# vca.net
KiCad netlist of a schematic drawn in EAGLE
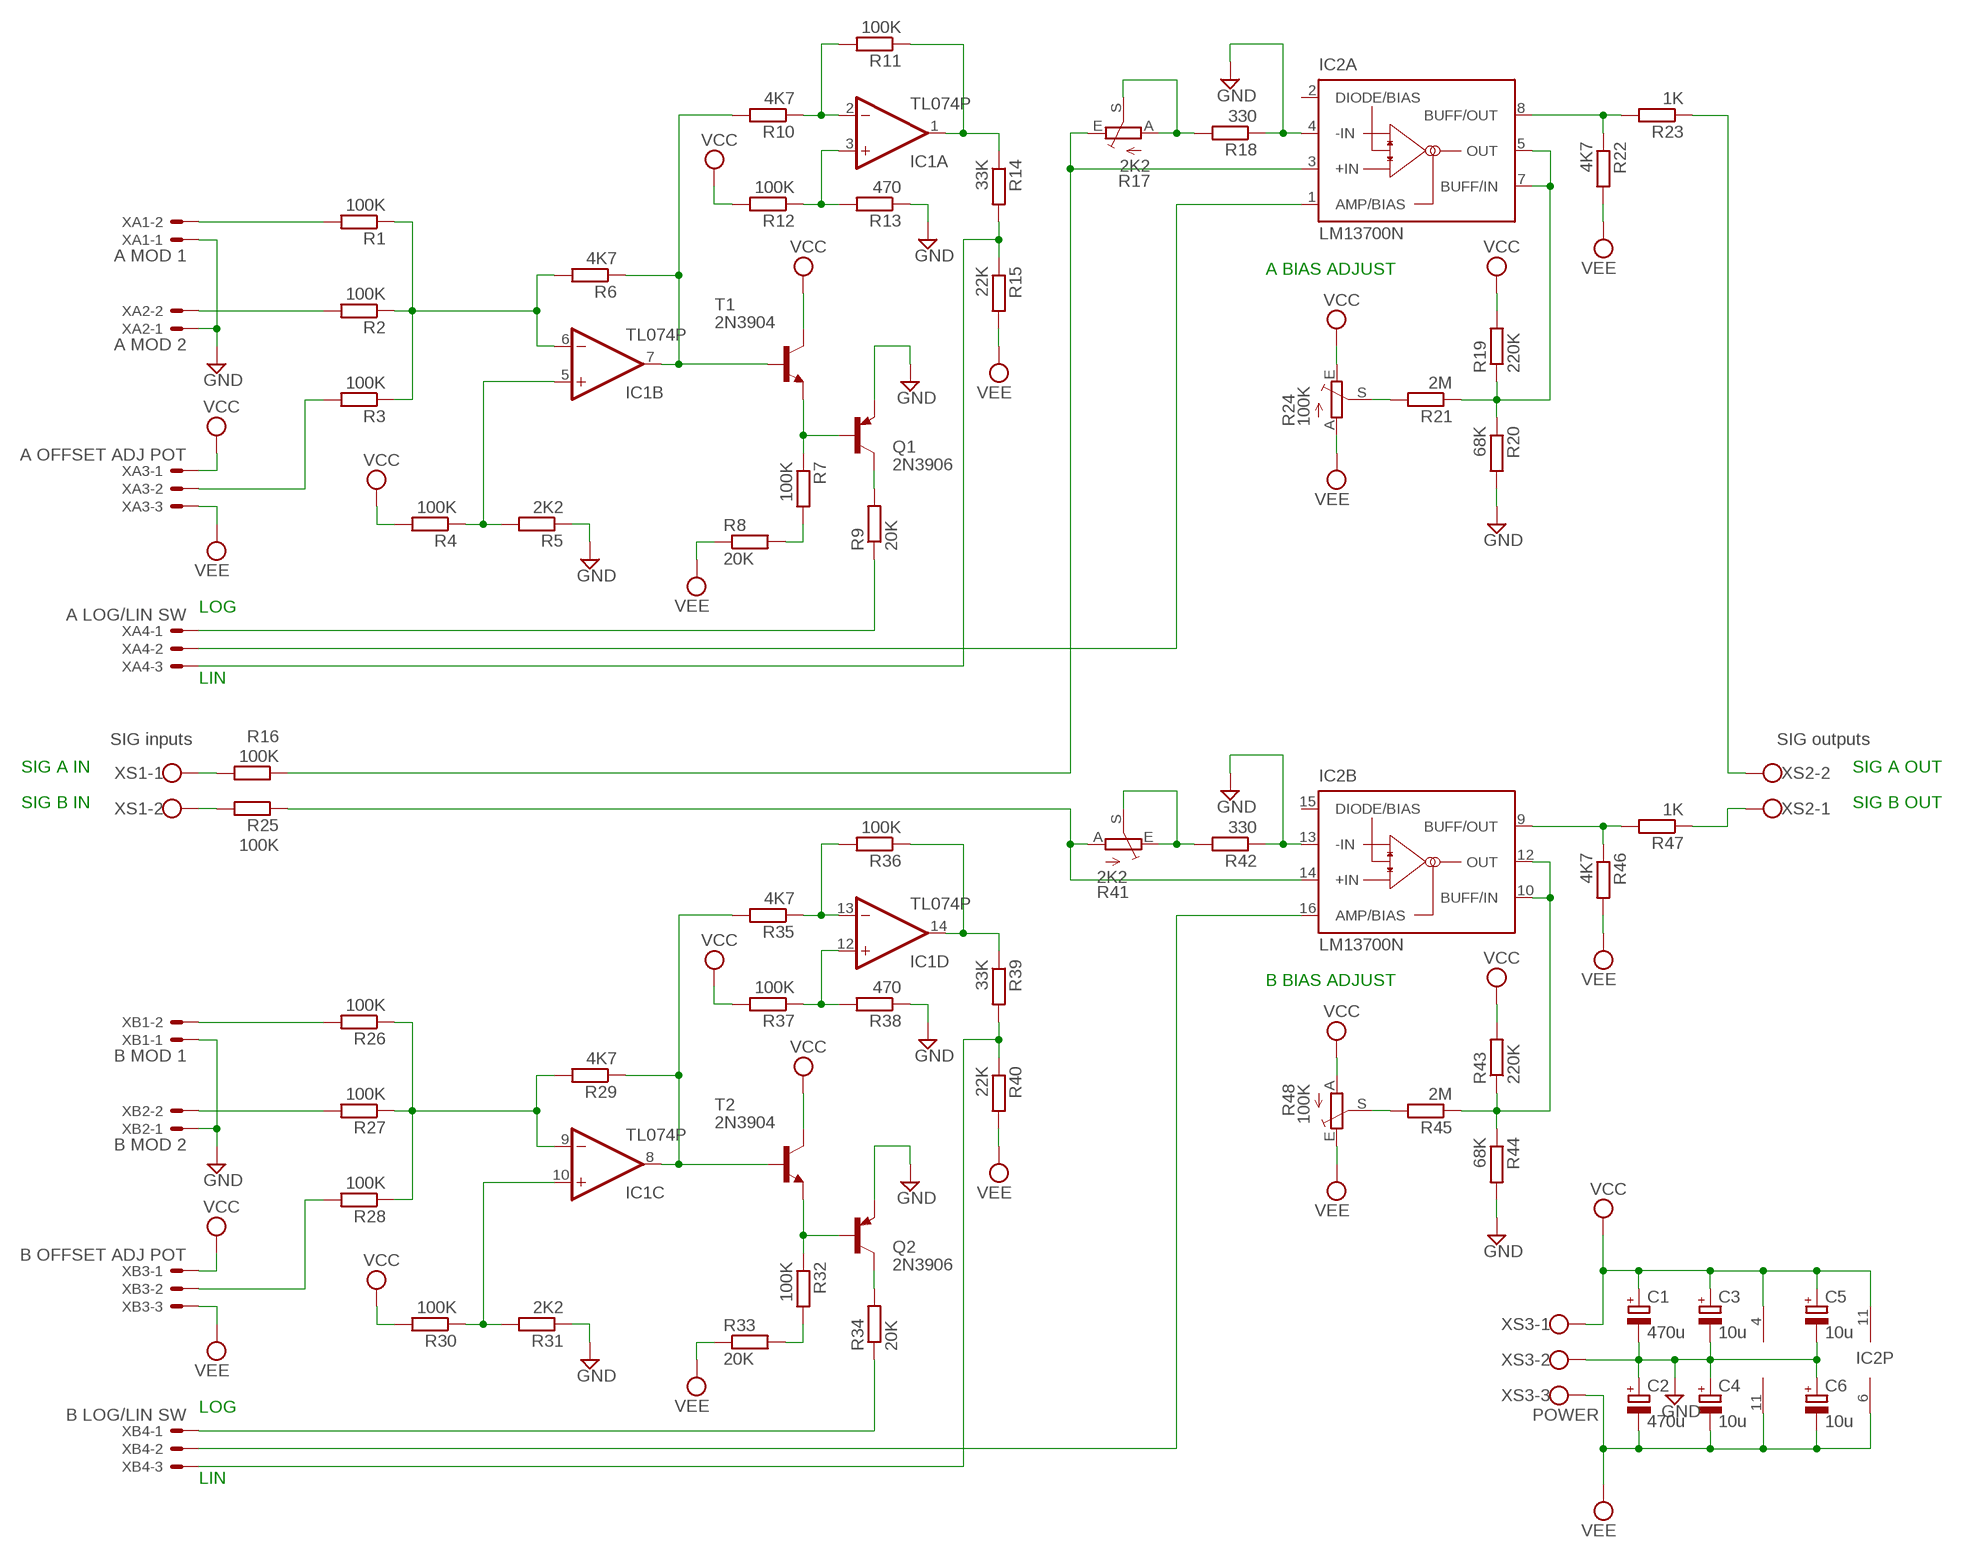
[diagram p0: schematic, sheet 1]

(export (version "E")
  (design (tool "Eeschema 10.0.6"))
  (components
    (comp (ref "C1")
      (value "470u")
      (footprint "eagle-import:E2,5-6")
      (libsource (lib "eagle-import") (part "CPOL-EUE2.5-6"))
    )
    (comp (ref "C2")
      (value "470u")
      (footprint "eagle-import:E2,5-6")
      (libsource (lib "eagle-import") (part "CPOL-EUE2.5-6"))
    )
    (comp (ref "C3")
      (value "10u")
      (footprint "eagle-import:E1,8-4")
      (libsource (lib "eagle-import") (part "CPOL-EUE1.8-4"))
    )
    (comp (ref "C4")
      (value "10u")
      (footprint "eagle-import:E1,8-4")
      (libsource (lib "eagle-import") (part "CPOL-EUE1.8-4"))
    )
    (comp (ref "C5")
      (value "10u")
      (footprint "eagle-import:E1,8-4")
      (libsource (lib "eagle-import") (part "CPOL-EUE1.8-4"))
    )
    (comp (ref "C6")
      (value "10u")
      (footprint "eagle-import:E1,8-4")
      (libsource (lib "eagle-import") (part "CPOL-EUE1.8-4"))
    )
    (comp (ref "IC1")
      (value "TL074P")
      (footprint "eagle-import:DIL14")
      (libsource (lib "eagle-import") (part "TL074P"))
    )
    (comp (ref "IC2")
      (value "LM13700N")
      (footprint "eagle-import:DIL16")
      (libsource (lib "eagle-import") (part "LM13600NA"))
    )
    (comp (ref "Q1")
      (value "2N3906")
      (footprint "eagle-import:TO92")
      (libsource (lib "eagle-import") (part "2N3906"))
    )
    (comp (ref "Q2")
      (value "2N3906")
      (footprint "eagle-import:TO92")
      (libsource (lib "eagle-import") (part "2N3906"))
    )
    (comp (ref "R1")
      (value "100K")
      (footprint "eagle-import:0204_7")
      (libsource (lib "eagle-import") (part "R-EU_0204/7"))
    )
    (comp (ref "R2")
      (value "100K")
      (footprint "eagle-import:0204_7")
      (libsource (lib "eagle-import") (part "R-EU_0204/7"))
    )
    (comp (ref "R3")
      (value "100K")
      (footprint "eagle-import:0204_7")
      (libsource (lib "eagle-import") (part "R-EU_0204/7"))
    )
    (comp (ref "R4")
      (value "100K")
      (footprint "eagle-import:0204_7")
      (libsource (lib "eagle-import") (part "R-EU_0204/7"))
    )
    (comp (ref "R5")
      (value "2K2")
      (footprint "eagle-import:0204_7")
      (libsource (lib "eagle-import") (part "R-EU_0204/7"))
    )
    (comp (ref "R6")
      (value "4K7")
      (footprint "eagle-import:0204_7")
      (libsource (lib "eagle-import") (part "R-EU_0204/7"))
    )
    (comp (ref "R7")
      (value "100K")
      (footprint "eagle-import:0204_7")
      (libsource (lib "eagle-import") (part "R-EU_0204/7"))
    )
    (comp (ref "R8")
      (value "20K")
      (footprint "eagle-import:0204_7")
      (libsource (lib "eagle-import") (part "R-EU_0204/7"))
    )
    (comp (ref "R9")
      (value "20K")
      (footprint "eagle-import:0204_7")
      (libsource (lib "eagle-import") (part "R-EU_0204/7"))
    )
    (comp (ref "R10")
      (value "4K7")
      (footprint "eagle-import:0204_7")
      (libsource (lib "eagle-import") (part "R-EU_0204/7"))
    )
    (comp (ref "R11")
      (value "100K")
      (footprint "eagle-import:0204_7")
      (libsource (lib "eagle-import") (part "R-EU_0204/7"))
    )
    (comp (ref "R12")
      (value "100K")
      (footprint "eagle-import:0204_7")
      (libsource (lib "eagle-import") (part "R-EU_0204/7"))
    )
    (comp (ref "R13")
      (value "470")
      (footprint "eagle-import:0204_7")
      (libsource (lib "eagle-import") (part "R-EU_0204/7"))
    )
    (comp (ref "R14")
      (value "33K")
      (footprint "eagle-import:0204_7")
      (libsource (lib "eagle-import") (part "R-EU_0204/7"))
    )
    (comp (ref "R15")
      (value "22K")
      (footprint "eagle-import:0204_7")
      (libsource (lib "eagle-import") (part "R-EU_0204/7"))
    )
    (comp (ref "R16")
      (value "100K")
      (footprint "eagle-import:0204_7")
      (libsource (lib "eagle-import") (part "R-EU_0204/7"))
    )
    (comp (ref "R17")
      (value "2K2")
      (footprint "eagle-import:CA6V")
      (libsource (lib "eagle-import") (part "TRIM_EU-CA6V"))
    )
    (comp (ref "R18")
      (value "330")
      (footprint "eagle-import:0204_7")
      (libsource (lib "eagle-import") (part "R-EU_0204/7"))
    )
    (comp (ref "R19")
      (value "220K")
      (footprint "eagle-import:0204_7")
      (libsource (lib "eagle-import") (part "R-EU_0204/7"))
    )
    (comp (ref "R20")
      (value "68K")
      (footprint "eagle-import:0204_7")
      (libsource (lib "eagle-import") (part "R-EU_0204/7"))
    )
    (comp (ref "R21")
      (value "2M")
      (footprint "eagle-import:0204_7")
      (libsource (lib "eagle-import") (part "R-EU_0204/7"))
    )
    (comp (ref "R22")
      (value "4K7")
      (footprint "eagle-import:0204_7")
      (libsource (lib "eagle-import") (part "R-EU_0204/7"))
    )
    (comp (ref "R23")
      (value "1K")
      (footprint "eagle-import:0204_7")
      (libsource (lib "eagle-import") (part "R-EU_0204/7"))
    )
    (comp (ref "R24")
      (value "100K")
      (footprint "eagle-import:CA6V")
      (libsource (lib "eagle-import") (part "TRIM_EU-CA6V"))
    )
    (comp (ref "R25")
      (value "100K")
      (footprint "eagle-import:0204_7")
      (libsource (lib "eagle-import") (part "R-EU_0204/7"))
    )
    (comp (ref "R26")
      (value "100K")
      (footprint "eagle-import:0204_7")
      (libsource (lib "eagle-import") (part "R-EU_0204/7"))
    )
    (comp (ref "R27")
      (value "100K")
      (footprint "eagle-import:0204_7")
      (libsource (lib "eagle-import") (part "R-EU_0204/7"))
    )
    (comp (ref "R28")
      (value "100K")
      (footprint "eagle-import:0204_7")
      (libsource (lib "eagle-import") (part "R-EU_0204/7"))
    )
    (comp (ref "R29")
      (value "4K7")
      (footprint "eagle-import:0204_7")
      (libsource (lib "eagle-import") (part "R-EU_0204/7"))
    )
    (comp (ref "R30")
      (value "100K")
      (footprint "eagle-import:0204_7")
      (libsource (lib "eagle-import") (part "R-EU_0204/7"))
    )
    (comp (ref "R31")
      (value "2K2")
      (footprint "eagle-import:0204_7")
      (libsource (lib "eagle-import") (part "R-EU_0204/7"))
    )
    (comp (ref "R32")
      (value "100K")
      (footprint "eagle-import:0204_7")
      (libsource (lib "eagle-import") (part "R-EU_0204/7"))
    )
    (comp (ref "R33")
      (value "20K")
      (footprint "eagle-import:0204_7")
      (libsource (lib "eagle-import") (part "R-EU_0204/7"))
    )
    (comp (ref "R34")
      (value "20K")
      (footprint "eagle-import:0204_7")
      (libsource (lib "eagle-import") (part "R-EU_0204/7"))
    )
    (comp (ref "R35")
      (value "4K7")
      (footprint "eagle-import:0204_7")
      (libsource (lib "eagle-import") (part "R-EU_0204/7"))
    )
    (comp (ref "R36")
      (value "100K")
      (footprint "eagle-import:0204_7")
      (libsource (lib "eagle-import") (part "R-EU_0204/7"))
    )
    (comp (ref "R37")
      (value "100K")
      (footprint "eagle-import:0204_7")
      (libsource (lib "eagle-import") (part "R-EU_0204/7"))
    )
    (comp (ref "R38")
      (value "470")
      (footprint "eagle-import:0204_7")
      (libsource (lib "eagle-import") (part "R-EU_0204/7"))
    )
    (comp (ref "R39")
      (value "33K")
      (footprint "eagle-import:0204_7")
      (libsource (lib "eagle-import") (part "R-EU_0204/7"))
    )
    (comp (ref "R40")
      (value "22K")
      (footprint "eagle-import:0204_7")
      (libsource (lib "eagle-import") (part "R-EU_0204/7"))
    )
    (comp (ref "R41")
      (value "2K2")
      (footprint "eagle-import:CA6V")
      (libsource (lib "eagle-import") (part "TRIM_EU-CA6V"))
    )
    (comp (ref "R42")
      (value "330")
      (footprint "eagle-import:0204_7")
      (libsource (lib "eagle-import") (part "R-EU_0204/7"))
    )
    (comp (ref "R43")
      (value "220K")
      (footprint "eagle-import:0204_7")
      (libsource (lib "eagle-import") (part "R-EU_0204/7"))
    )
    (comp (ref "R44")
      (value "68K")
      (footprint "eagle-import:0204_7")
      (libsource (lib "eagle-import") (part "R-EU_0204/7"))
    )
    (comp (ref "R45")
      (value "2M")
      (footprint "eagle-import:0204_7")
      (libsource (lib "eagle-import") (part "R-EU_0204/7"))
    )
    (comp (ref "R46")
      (value "4K7")
      (footprint "eagle-import:0204_7")
      (libsource (lib "eagle-import") (part "R-EU_0204/7"))
    )
    (comp (ref "R47")
      (value "1K")
      (footprint "eagle-import:0204_7")
      (libsource (lib "eagle-import") (part "R-EU_0204/7"))
    )
    (comp (ref "R48")
      (value "100K")
      (footprint "eagle-import:CA6V")
      (libsource (lib "eagle-import") (part "TRIM_EU-CA6V"))
    )
    (comp (ref "T1")
      (value "2N3904")
      (footprint "eagle-import:TO92")
      (libsource (lib "eagle-import") (part "2N3904"))
    )
    (comp (ref "T2")
      (value "2N3904")
      (footprint "eagle-import:TO92")
      (libsource (lib "eagle-import") (part "2N3904"))
    )
    (comp (ref "XA1")
      (value "A MOD 1")
      (footprint "eagle-import:22-23-2021")
      (fields (field (name "MF") "MOLEX") (field (name "MPN") "22-23-2021"))
      (libsource (lib "eagle-import") (part "22-23-2021"))
    )
    (comp (ref "XA2")
      (value "A MOD 2")
      (footprint "eagle-import:22-23-2021")
      (fields (field (name "MF") "MOLEX") (field (name "MPN") "22-23-2021"))
      (libsource (lib "eagle-import") (part "22-23-2021"))
    )
    (comp (ref "XA3")
      (value "A OFFSET ADJ POT")
      (footprint "eagle-import:22-23-2031")
      (fields (field (name "MF") "MOLEX") (field (name "MPN") "22-23-2031"))
      (libsource (lib "eagle-import") (part "22-23-2031"))
    )
    (comp (ref "XA4")
      (value "A LOG/LIN SW")
      (footprint "eagle-import:22-23-2031")
      (fields (field (name "MF") "MOLEX") (field (name "MPN") "22-23-2031"))
      (libsource (lib "eagle-import") (part "22-23-2031"))
    )
    (comp (ref "XB1")
      (value "B MOD 1")
      (footprint "eagle-import:22-23-2021")
      (fields (field (name "MF") "MOLEX") (field (name "MPN") "22-23-2021"))
      (libsource (lib "eagle-import") (part "22-23-2021"))
    )
    (comp (ref "XB2")
      (value "B MOD 2")
      (footprint "eagle-import:22-23-2021")
      (fields (field (name "MF") "MOLEX") (field (name "MPN") "22-23-2021"))
      (libsource (lib "eagle-import") (part "22-23-2021"))
    )
    (comp (ref "XB3")
      (value "B OFFSET ADJ POT")
      (footprint "eagle-import:22-23-2031")
      (fields (field (name "MF") "MOLEX") (field (name "MPN") "22-23-2031"))
      (libsource (lib "eagle-import") (part "22-23-2031"))
    )
    (comp (ref "XB4")
      (value "B LOG/LIN SW")
      (footprint "eagle-import:22-23-2031")
      (fields (field (name "MF") "MOLEX") (field (name "MPN") "22-23-2031"))
      (libsource (lib "eagle-import") (part "22-23-2031"))
    )
    (comp (ref "XS1")
      (value "SIG inputs")
      (footprint "eagle-import:W237-102")
      (fields (field (name "MPN") "237-102"))
      (libsource (lib "eagle-import") (part "W237-102"))
    )
    (comp (ref "XS2")
      (value "SIG outputs")
      (footprint "eagle-import:W237-102")
      (fields (field (name "MPN") "237-102"))
      (libsource (lib "eagle-import") (part "W237-102"))
    )
    (comp (ref "XS3")
      (value "POWER")
      (footprint "eagle-import:W237-103")
      (fields (field (name "MPN") "237-103"))
      (libsource (lib "eagle-import") (part "W237-103"))
    )
  )
  (nets
    (net (code "1") (name "GND") (class "Default")
      (node (ref "C1") (pin "-") (pinfunction "-_-") (pintype "passive"))
      (node (ref "C2") (pin "+") (pinfunction "+_+") (pintype "passive"))
      (node (ref "C3") (pin "-") (pinfunction "-_-") (pintype "passive"))
      (node (ref "C4") (pin "+") (pinfunction "+_+") (pintype "passive"))
      (node (ref "C5") (pin "-") (pinfunction "-_-") (pintype "passive"))
      (node (ref "C6") (pin "+") (pinfunction "+_+") (pintype "passive"))
      (node (ref "IC2") (pin "13") (pinfunction "-IN_13") (pintype "input"))
      (node (ref "IC2") (pin "4") (pinfunction "-IN_4") (pintype "input"))
      (node (ref "Q1") (pin "3") (pinfunction "E_3") (pintype "passive"))
      (node (ref "Q2") (pin "3") (pinfunction "E_3") (pintype "passive"))
      (node (ref "R13") (pin "1") (pinfunction "1_1") (pintype "passive"))
      (node (ref "R18") (pin "1") (pinfunction "1_1") (pintype "passive"))
      (node (ref "R20") (pin "2") (pinfunction "2_2") (pintype "passive"))
      (node (ref "R31") (pin "1") (pinfunction "1_1") (pintype "passive"))
      (node (ref "R38") (pin "1") (pinfunction "1_1") (pintype "passive"))
      (node (ref "R42") (pin "1") (pinfunction "1_1") (pintype "passive"))
      (node (ref "R44") (pin "2") (pinfunction "2_2") (pintype "passive"))
      (node (ref "R5") (pin "1") (pinfunction "1_1") (pintype "passive"))
      (node (ref "XA1") (pin "1") (pinfunction "S_1") (pintype "passive"))
      (node (ref "XA2") (pin "1") (pinfunction "S_1") (pintype "passive"))
      (node (ref "XB1") (pin "1") (pinfunction "S_1") (pintype "passive"))
      (node (ref "XB2") (pin "1") (pinfunction "S_1") (pintype "passive"))
      (node (ref "XS3") (pin "2") (pinfunction "KL_2") (pintype "passive"))
    )
    (net (code "2") (name "Net-(IC1A-+IN)") (class "Default")
      (node (ref "IC1") (pin "3") (pinfunction "+IN_3") (pintype "input"))
      (node (ref "R12") (pin "1") (pinfunction "1_1") (pintype "passive"))
      (node (ref "R13") (pin "2") (pinfunction "2_2") (pintype "passive"))
    )
    (net (code "3") (name "Net-(IC1A--IN)") (class "Default")
      (node (ref "IC1") (pin "2") (pinfunction "-IN_2") (pintype "input"))
      (node (ref "R10") (pin "1") (pinfunction "1_1") (pintype "passive"))
      (node (ref "R11") (pin "2") (pinfunction "2_2") (pintype "passive"))
    )
    (net (code "4") (name "Net-(IC1A-OUT)") (class "Default")
      (node (ref "IC1") (pin "1") (pinfunction "OUT_1") (pintype "output"))
      (node (ref "R11") (pin "1") (pinfunction "1_1") (pintype "passive"))
      (node (ref "R14") (pin "1") (pinfunction "1_1") (pintype "passive"))
    )
    (net (code "5") (name "Net-(IC1B-+IN)") (class "Default")
      (node (ref "IC1") (pin "5") (pinfunction "+IN_5") (pintype "input"))
      (node (ref "R4") (pin "1") (pinfunction "1_1") (pintype "passive"))
      (node (ref "R5") (pin "2") (pinfunction "2_2") (pintype "passive"))
    )
    (net (code "6") (name "Net-(IC1B--IN)") (class "Default")
      (node (ref "IC1") (pin "6") (pinfunction "-IN_6") (pintype "input"))
      (node (ref "R1") (pin "1") (pinfunction "1_1") (pintype "passive"))
      (node (ref "R2") (pin "1") (pinfunction "1_1") (pintype "passive"))
      (node (ref "R3") (pin "1") (pinfunction "1_1") (pintype "passive"))
      (node (ref "R6") (pin "2") (pinfunction "2_2") (pintype "passive"))
    )
    (net (code "7") (name "Net-(IC1B-OUT)") (class "Default")
      (node (ref "IC1") (pin "7") (pinfunction "OUT_7") (pintype "output"))
      (node (ref "R10") (pin "2") (pinfunction "2_2") (pintype "passive"))
      (node (ref "R6") (pin "1") (pinfunction "1_1") (pintype "passive"))
      (node (ref "T1") (pin "2") (pinfunction "B_2") (pintype "passive"))
    )
    (net (code "8") (name "Net-(IC1C-+IN)") (class "Default")
      (node (ref "IC1") (pin "10") (pinfunction "+IN_10") (pintype "input"))
      (node (ref "R30") (pin "1") (pinfunction "1_1") (pintype "passive"))
      (node (ref "R31") (pin "2") (pinfunction "2_2") (pintype "passive"))
    )
    (net (code "9") (name "Net-(IC1C--IN)") (class "Default")
      (node (ref "IC1") (pin "9") (pinfunction "-IN_9") (pintype "input"))
      (node (ref "R26") (pin "1") (pinfunction "1_1") (pintype "passive"))
      (node (ref "R27") (pin "1") (pinfunction "1_1") (pintype "passive"))
      (node (ref "R28") (pin "1") (pinfunction "1_1") (pintype "passive"))
      (node (ref "R29") (pin "2") (pinfunction "2_2") (pintype "passive"))
    )
    (net (code "10") (name "Net-(IC1C-OUT)") (class "Default")
      (node (ref "IC1") (pin "8") (pinfunction "OUT_8") (pintype "output"))
      (node (ref "R29") (pin "1") (pinfunction "1_1") (pintype "passive"))
      (node (ref "R35") (pin "2") (pinfunction "2_2") (pintype "passive"))
      (node (ref "T2") (pin "2") (pinfunction "B_2") (pintype "passive"))
    )
    (net (code "11") (name "Net-(IC1D-+IN)") (class "Default")
      (node (ref "IC1") (pin "12") (pinfunction "+IN_12") (pintype "input"))
      (node (ref "R37") (pin "1") (pinfunction "1_1") (pintype "passive"))
      (node (ref "R38") (pin "2") (pinfunction "2_2") (pintype "passive"))
    )
    (net (code "12") (name "Net-(IC1D--IN)") (class "Default")
      (node (ref "IC1") (pin "13") (pinfunction "-IN_13") (pintype "input"))
      (node (ref "R35") (pin "1") (pinfunction "1_1") (pintype "passive"))
      (node (ref "R36") (pin "2") (pinfunction "2_2") (pintype "passive"))
    )
    (net (code "13") (name "Net-(IC1D-OUT)") (class "Default")
      (node (ref "IC1") (pin "14") (pinfunction "OUT_14") (pintype "output"))
      (node (ref "R36") (pin "1") (pinfunction "1_1") (pintype "passive"))
      (node (ref "R39") (pin "1") (pinfunction "1_1") (pintype "passive"))
    )
    (net (code "14") (name "Net-(IC2A-+IN)") (class "Default")
      (node (ref "IC2") (pin "3") (pinfunction "+IN_3") (pintype "input"))
      (node (ref "R16") (pin "1") (pinfunction "1_1") (pintype "passive"))
      (node (ref "R17") (pin "E") (pinfunction "E_E") (pintype "passive"))
    )
    (net (code "15") (name "Net-(IC2A-AMP{slash}BIAS)") (class "Default")
      (node (ref "IC2") (pin "1") (pinfunction "AMP/BIAS_1") (pintype "passive"))
      (node (ref "XA4") (pin "2") (pinfunction "S_2") (pintype "passive"))
    )
    (net (code "16") (name "Net-(IC2A-BUFF{slash}IN)") (class "Default")
      (node (ref "IC2") (pin "5") (pinfunction "OUT_5") (pintype "output"))
      (node (ref "IC2") (pin "7") (pinfunction "BUFF/IN_7") (pintype "input"))
      (node (ref "R19") (pin "1") (pinfunction "1_1") (pintype "passive"))
      (node (ref "R20") (pin "1") (pinfunction "1_1") (pintype "passive"))
      (node (ref "R21") (pin "1") (pinfunction "1_1") (pintype "passive"))
    )
    (net (code "17") (name "Net-(IC2A-BUFF{slash}OUT)") (class "Default")
      (node (ref "IC2") (pin "8") (pinfunction "BUFF/OUT_8") (pintype "output"))
      (node (ref "R22") (pin "1") (pinfunction "1_1") (pintype "passive"))
      (node (ref "R23") (pin "2") (pinfunction "2_2") (pintype "passive"))
    )
    (net (code "18") (name "Net-(IC2B-+IN)") (class "Default")
      (node (ref "IC2") (pin "14") (pinfunction "+IN_14") (pintype "input"))
      (node (ref "R25") (pin "1") (pinfunction "1_1") (pintype "passive"))
      (node (ref "R41") (pin "A") (pinfunction "A_A") (pintype "passive"))
    )
    (net (code "19") (name "Net-(IC2B-AMP{slash}BIAS)") (class "Default")
      (node (ref "IC2") (pin "16") (pinfunction "AMP/BIAS_16") (pintype "passive"))
      (node (ref "XB4") (pin "2") (pinfunction "S_2") (pintype "passive"))
    )
    (net (code "20") (name "Net-(IC2B-BUFF{slash}IN)") (class "Default")
      (node (ref "IC2") (pin "10") (pinfunction "BUFF/IN_10") (pintype "input"))
      (node (ref "IC2") (pin "12") (pinfunction "OUT_12") (pintype "output"))
      (node (ref "R43") (pin "1") (pinfunction "1_1") (pintype "passive"))
      (node (ref "R44") (pin "1") (pinfunction "1_1") (pintype "passive"))
      (node (ref "R45") (pin "1") (pinfunction "1_1") (pintype "passive"))
    )
    (net (code "21") (name "Net-(IC2B-BUFF{slash}OUT)") (class "Default")
      (node (ref "IC2") (pin "9") (pinfunction "BUFF/OUT_9") (pintype "output"))
      (node (ref "R46") (pin "1") (pinfunction "1_1") (pintype "passive"))
      (node (ref "R47") (pin "2") (pinfunction "2_2") (pintype "passive"))
    )
    (net (code "22") (name "Net-(Q1-B)") (class "Default")
      (node (ref "Q1") (pin "2") (pinfunction "B_2") (pintype "passive"))
      (node (ref "R7") (pin "1") (pinfunction "1_1") (pintype "passive"))
      (node (ref "T1") (pin "3") (pinfunction "E_3") (pintype "passive"))
    )
    (net (code "23") (name "Net-(Q1-C)") (class "Default")
      (node (ref "Q1") (pin "1") (pinfunction "C_1") (pintype "passive"))
      (node (ref "R9") (pin "2") (pinfunction "2_2") (pintype "passive"))
    )
    (net (code "24") (name "Net-(Q2-B)") (class "Default")
      (node (ref "Q2") (pin "2") (pinfunction "B_2") (pintype "passive"))
      (node (ref "R32") (pin "1") (pinfunction "1_1") (pintype "passive"))
      (node (ref "T2") (pin "3") (pinfunction "E_3") (pintype "passive"))
    )
    (net (code "25") (name "Net-(Q2-C)") (class "Default")
      (node (ref "Q2") (pin "1") (pinfunction "C_1") (pintype "passive"))
      (node (ref "R34") (pin "2") (pinfunction "2_2") (pintype "passive"))
    )
    (net (code "26") (name "Net-(R7-Pad2)") (class "Default")
      (node (ref "R7") (pin "2") (pinfunction "2_2") (pintype "passive"))
      (node (ref "R8") (pin "2") (pinfunction "2_2") (pintype "passive"))
    )
    (net (code "27") (name "Net-(R17-PadA)") (class "Default")
      (node (ref "R17") (pin "A") (pinfunction "A_A") (pintype "passive"))
      (node (ref "R17") (pin "S") (pinfunction "S_S") (pintype "passive"))
      (node (ref "R18") (pin "2") (pinfunction "2_2") (pintype "passive"))
    )
    (net (code "28") (name "Net-(R21-Pad2)") (class "Default")
      (node (ref "R21") (pin "2") (pinfunction "2_2") (pintype "passive"))
      (node (ref "R24") (pin "S") (pinfunction "S_S") (pintype "passive"))
    )
    (net (code "29") (name "Net-(R32-Pad2)") (class "Default")
      (node (ref "R32") (pin "2") (pinfunction "2_2") (pintype "passive"))
      (node (ref "R33") (pin "2") (pinfunction "2_2") (pintype "passive"))
    )
    (net (code "30") (name "Net-(R41-PadE)") (class "Default")
      (node (ref "R41") (pin "E") (pinfunction "E_E") (pintype "passive"))
      (node (ref "R41") (pin "S") (pinfunction "S_S") (pintype "passive"))
      (node (ref "R42") (pin "2") (pinfunction "2_2") (pintype "passive"))
    )
    (net (code "31") (name "Net-(R45-Pad2)") (class "Default")
      (node (ref "R45") (pin "2") (pinfunction "2_2") (pintype "passive"))
      (node (ref "R48") (pin "S") (pinfunction "S_S") (pintype "passive"))
    )
    (net (code "32") (name "Net-(XA1B-S)") (class "Default")
      (node (ref "R1") (pin "2") (pinfunction "2_2") (pintype "passive"))
      (node (ref "XA1") (pin "2") (pinfunction "S_2") (pintype "passive"))
    )
    (net (code "33") (name "Net-(XA2B-S)") (class "Default")
      (node (ref "R2") (pin "2") (pinfunction "2_2") (pintype "passive"))
      (node (ref "XA2") (pin "2") (pinfunction "S_2") (pintype "passive"))
    )
    (net (code "34") (name "Net-(XA3B-S)") (class "Default")
      (node (ref "R3") (pin "2") (pinfunction "2_2") (pintype "passive"))
      (node (ref "XA3") (pin "2") (pinfunction "S_2") (pintype "passive"))
    )
    (net (code "35") (name "Net-(XA4A-S)") (class "Default")
      (node (ref "R9") (pin "1") (pinfunction "1_1") (pintype "passive"))
      (node (ref "XA4") (pin "1") (pinfunction "S_1") (pintype "passive"))
    )
    (net (code "36") (name "Net-(XA4C-S)") (class "Default")
      (node (ref "R14") (pin "2") (pinfunction "2_2") (pintype "passive"))
      (node (ref "R15") (pin "1") (pinfunction "1_1") (pintype "passive"))
      (node (ref "XA4") (pin "3") (pinfunction "S_3") (pintype "passive"))
    )
    (net (code "37") (name "Net-(XB1B-S)") (class "Default")
      (node (ref "R26") (pin "2") (pinfunction "2_2") (pintype "passive"))
      (node (ref "XB1") (pin "2") (pinfunction "S_2") (pintype "passive"))
    )
    (net (code "38") (name "Net-(XB2B-S)") (class "Default")
      (node (ref "R27") (pin "2") (pinfunction "2_2") (pintype "passive"))
      (node (ref "XB2") (pin "2") (pinfunction "S_2") (pintype "passive"))
    )
    (net (code "39") (name "Net-(XB3B-S)") (class "Default")
      (node (ref "R28") (pin "2") (pinfunction "2_2") (pintype "passive"))
      (node (ref "XB3") (pin "2") (pinfunction "S_2") (pintype "passive"))
    )
    (net (code "40") (name "Net-(XB4A-S)") (class "Default")
      (node (ref "R34") (pin "1") (pinfunction "1_1") (pintype "passive"))
      (node (ref "XB4") (pin "1") (pinfunction "S_1") (pintype "passive"))
    )
    (net (code "41") (name "Net-(XB4C-S)") (class "Default")
      (node (ref "R39") (pin "2") (pinfunction "2_2") (pintype "passive"))
      (node (ref "R40") (pin "1") (pinfunction "1_1") (pintype "passive"))
      (node (ref "XB4") (pin "3") (pinfunction "S_3") (pintype "passive"))
    )
    (net (code "42") (name "Net-(XS1A-KL)") (class "Default")
      (node (ref "R16") (pin "2") (pinfunction "2_2") (pintype "passive"))
      (node (ref "XS1") (pin "1") (pinfunction "KL_1") (pintype "passive"))
    )
    (net (code "43") (name "Net-(XS1B-KL)") (class "Default")
      (node (ref "R25") (pin "2") (pinfunction "2_2") (pintype "passive"))
      (node (ref "XS1") (pin "2") (pinfunction "KL_2") (pintype "passive"))
    )
    (net (code "44") (name "Net-(XS2A-KL)") (class "Default")
      (node (ref "R47") (pin "1") (pinfunction "1_1") (pintype "passive"))
      (node (ref "XS2") (pin "1") (pinfunction "KL_1") (pintype "passive"))
    )
    (net (code "45") (name "Net-(XS2B-KL)") (class "Default")
      (node (ref "R23") (pin "1") (pinfunction "1_1") (pintype "passive"))
      (node (ref "XS2") (pin "2") (pinfunction "KL_2") (pintype "passive"))
    )
    (net (code "46") (name "VCC") (class "Default")
      (node (ref "C1") (pin "+") (pinfunction "+_+") (pintype "passive"))
      (node (ref "C3") (pin "+") (pinfunction "+_+") (pintype "passive"))
      (node (ref "C5") (pin "+") (pinfunction "+_+") (pintype "passive"))
      (node (ref "IC1") (pin "4") (pinfunction "V+_4") (pintype "power_in"))
      (node (ref "IC2") (pin "11") (pinfunction "V+_11") (pintype "power_in"))
      (node (ref "R12") (pin "2") (pinfunction "2_2") (pintype "passive"))
      (node (ref "R19") (pin "2") (pinfunction "2_2") (pintype "passive"))
      (node (ref "R24") (pin "E") (pinfunction "E_E") (pintype "passive"))
      (node (ref "R30") (pin "2") (pinfunction "2_2") (pintype "passive"))
      (node (ref "R37") (pin "2") (pinfunction "2_2") (pintype "passive"))
      (node (ref "R4") (pin "2") (pinfunction "2_2") (pintype "passive"))
      (node (ref "R43") (pin "2") (pinfunction "2_2") (pintype "passive"))
      (node (ref "R48") (pin "A") (pinfunction "A_A") (pintype "passive"))
      (node (ref "T1") (pin "1") (pinfunction "C_1") (pintype "passive"))
      (node (ref "T2") (pin "1") (pinfunction "C_1") (pintype "passive"))
      (node (ref "XA3") (pin "1") (pinfunction "S_1") (pintype "passive"))
      (node (ref "XB3") (pin "1") (pinfunction "S_1") (pintype "passive"))
      (node (ref "XS3") (pin "1") (pinfunction "KL_1") (pintype "passive"))
    )
    (net (code "47") (name "VEE") (class "Default")
      (node (ref "C2") (pin "-") (pinfunction "-_-") (pintype "passive"))
      (node (ref "C4") (pin "-") (pinfunction "-_-") (pintype "passive"))
      (node (ref "C6") (pin "-") (pinfunction "-_-") (pintype "passive"))
      (node (ref "IC1") (pin "11") (pinfunction "V-_11") (pintype "power_in"))
      (node (ref "IC2") (pin "6") (pinfunction "V-_6") (pintype "power_in"))
      (node (ref "R15") (pin "2") (pinfunction "2_2") (pintype "passive"))
      (node (ref "R22") (pin "2") (pinfunction "2_2") (pintype "passive"))
      (node (ref "R24") (pin "A") (pinfunction "A_A") (pintype "passive"))
      (node (ref "R33") (pin "1") (pinfunction "1_1") (pintype "passive"))
      (node (ref "R40") (pin "2") (pinfunction "2_2") (pintype "passive"))
      (node (ref "R46") (pin "2") (pinfunction "2_2") (pintype "passive"))
      (node (ref "R48") (pin "E") (pinfunction "E_E") (pintype "passive"))
      (node (ref "R8") (pin "1") (pinfunction "1_1") (pintype "passive"))
      (node (ref "XA3") (pin "3") (pinfunction "S_3") (pintype "passive"))
      (node (ref "XB3") (pin "3") (pinfunction "S_3") (pintype "passive"))
      (node (ref "XS3") (pin "3") (pinfunction "KL_3") (pintype "passive"))
    )
    (net (code "48") (name "unconnected-(IC2A-DIODE{slash}BIAS-Pad2)") (class "Default")
      (node (ref "IC2") (pin "2") (pinfunction "DIODE/BIAS_2") (pintype "passive"))
    )
    (net (code "49") (name "unconnected-(IC2B-DIODE{slash}BIAS-Pad15)") (class "Default")
      (node (ref "IC2") (pin "15") (pinfunction "DIODE/BIAS_15") (pintype "passive"))
    )
  )
)
